# STM32_IO.net
KiCad netlist of a schematic drawn in Altium Designer
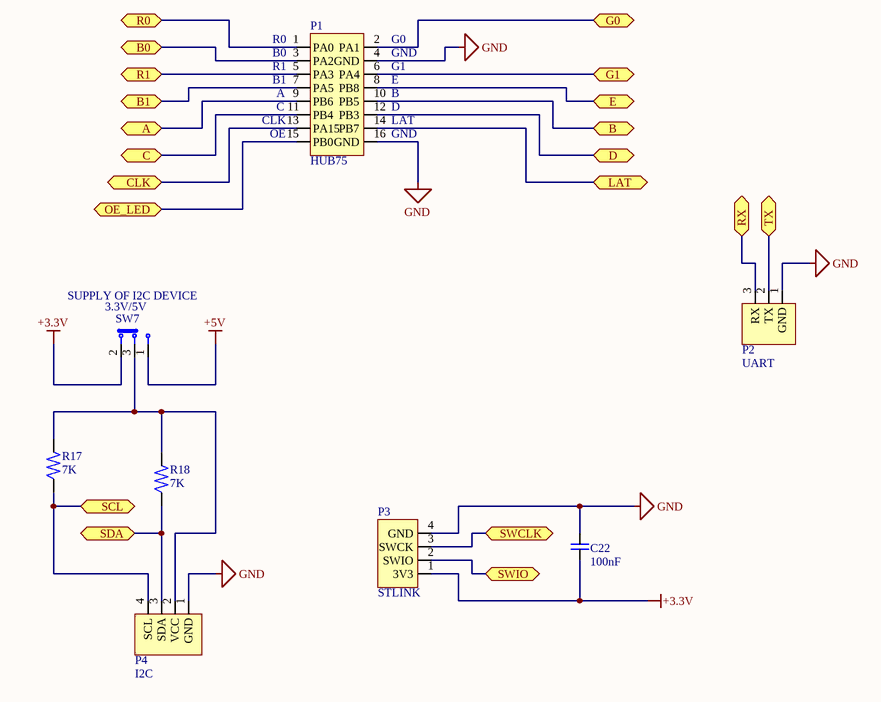
[diagram p0: STM32_IO.SchDoc]

(export (version "E")
  (design (tool "Eeschema 10.0.6"))
  (components
    (comp (ref "C22")
      (value "100nF")
      (footprint "SMT_CAP_MODEL_1206(3216)_SAMSUNG")
      (description "SMT Samsung Ceramic Capacitor MODEL *V *nF 1206(3216)  CL31B104KBCNNNC(etc.)")
      (libsource (lib "SMT_CAP_MODEL_1206(3216)_SAMSUNG") (part "SMT_CAP_MODEL_1206(3216)_SAMSUNG"))
    )
    (comp (ref "P1")
      (value "HUB75")
      (footprint "THT_CON_2316S-16G")
      (description "Connector 2316S-16G 16 Pin 2.54 Pitch")
      (libsource (lib "THT_CON_2316S-16G") (part "THT_CON_2316S-16G"))
    )
    (comp (ref "P2")
      (value "UART")
      (footprint "SMT_CON_STRAIGHT_2417SJ-03-SM2")
      (description "Connector 3P NELTRON 2417SJ-03-SM2-CR 100V/2A 2.0mm Pitch SMT")
      (libsource (lib "SMT_CON_STRAIGHT_2417SJ-03-SM2") (part "SMT_CON_STRAIGHT_2417SJ-03-SM2"))
    )
    (comp (ref "P3")
      (value "STLINK")
      (footprint "THT_STLINK_HEADER_4P_MALE")
      (description "Dupont Header Male STLINK 4P 2.54 Pitch")
      (libsource (lib "THT_STLINK_HEADER_4P_MALE") (part "THT_STLINK_HEADER_4P_MALE"))
    )
    (comp (ref "P4")
      (value "I2C")
      (footprint "SMT_CON_STRAIGHT_2417SJ-04-SM2")
      (description "Connector 4P NELTRON 2417SJ-04-SM2-CR 100V/2A 2.0mm Pitch SMT")
      (libsource (lib "SMT_CON_STRAIGHT_2417SJ-04-SM2") (part "SMT_CON_STRAIGHT_2417SJ-04-SM2"))
    )
    (comp (ref "R17")
      (value "7K")
      (footprint "SMT_RES_MODEL_1206(3216)_ROHM")
      (description "SMT ROHM Resistor MODEL 1206(3216) 1/4W MCR18ERTJ000")
      (libsource (lib "SMT_RES_MODEL_1206(3216)_ROHM") (part "SMT_RES_MODEL_1206(3216)_ROHM"))
    )
    (comp (ref "R18")
      (value "7K")
      (footprint "SMT_RES_MODEL_1206(3216)_ROHM")
      (description "SMT ROHM Resistor MODEL 1206(3216) 1/4W MCR18ERTJ000")
      (libsource (lib "SMT_RES_MODEL_1206(3216)_ROHM") (part "SMT_RES_MODEL_1206(3216)_ROHM"))
    )
    (comp (ref "SW7")
      (value "3.3V/5V")
      (footprint "THT_SSW_ESP1010")
      (description "Slide Switch ESP1010 12V 0.5A")
      (libsource (lib "THT_SSW_ESP1010") (part "THT_SSW_ESP1010"))
    )
  )
  (nets
    (net (code "1") (name "+3.3V") (class "Default")
      (node (ref "C22") (pin "1") (pinfunction "1_1") (pintype "passive"))
      (node (ref "P3") (pin "1") (pinfunction "3V3_1") (pintype "passive"))
      (node (ref "SW7") (pin "2") (pinfunction "2_2") (pintype "passive"))
    )
    (net (code "2") (name "+5V") (class "Default")
      (node (ref "SW7") (pin "1") (pinfunction "1_1") (pintype "passive"))
    )
    (net (code "3") (name "/A") (class "Default")
      (node (ref "P1") (pin "9") (pinfunction "PB6_9") (pintype "passive"))
    )
    (net (code "4") (name "/B") (class "Default")
      (node (ref "P1") (pin "10") (pinfunction "PB5_10") (pintype "passive"))
    )
    (net (code "5") (name "/B0") (class "Default")
      (node (ref "P1") (pin "3") (pinfunction "PA2_3") (pintype "passive"))
    )
    (net (code "6") (name "/B1") (class "Default")
      (node (ref "P1") (pin "7") (pinfunction "PA5_7") (pintype "passive"))
    )
    (net (code "7") (name "/C") (class "Default")
      (node (ref "P1") (pin "11") (pinfunction "PB4_11") (pintype "passive"))
    )
    (net (code "8") (name "/CLK") (class "Default")
      (node (ref "P1") (pin "13") (pinfunction "PA15_13") (pintype "passive"))
    )
    (net (code "9") (name "/D") (class "Default")
      (node (ref "P1") (pin "12") (pinfunction "PB3_12") (pintype "passive"))
    )
    (net (code "10") (name "/E") (class "Default")
      (node (ref "P1") (pin "8") (pinfunction "PB8_8") (pintype "passive"))
    )
    (net (code "11") (name "/G0") (class "Default")
      (node (ref "P1") (pin "2") (pinfunction "PA1_2") (pintype "passive"))
    )
    (net (code "12") (name "/G1") (class "Default")
      (node (ref "P1") (pin "6") (pinfunction "PA4_6") (pintype "passive"))
    )
    (net (code "13") (name "/LAT") (class "Default")
      (node (ref "P1") (pin "14") (pinfunction "PB7_14") (pintype "passive"))
    )
    (net (code "14") (name "/OE_LED") (class "Default")
      (node (ref "P1") (pin "15") (pinfunction "PB0_15") (pintype "passive"))
    )
    (net (code "15") (name "/R0") (class "Default")
      (node (ref "P1") (pin "1") (pinfunction "PA0_1") (pintype "passive"))
    )
    (net (code "16") (name "/R1") (class "Default")
      (node (ref "P1") (pin "5") (pinfunction "PA3_5") (pintype "passive"))
    )
    (net (code "17") (name "/RX") (class "Default")
      (node (ref "P2") (pin "3") (pinfunction "RX_3") (pintype "passive"))
    )
    (net (code "18") (name "/SCL") (class "Default")
      (node (ref "P4") (pin "4") (pinfunction "SCL_4") (pintype "passive"))
      (node (ref "R17") (pin "2") (pinfunction "2_2") (pintype "passive"))
    )
    (net (code "19") (name "/SDA") (class "Default")
      (node (ref "P4") (pin "3") (pinfunction "SDA_3") (pintype "passive"))
      (node (ref "R18") (pin "2") (pinfunction "2_2") (pintype "passive"))
    )
    (net (code "20") (name "/SWCLK") (class "Default")
      (node (ref "P3") (pin "3") (pinfunction "SWCK_3") (pintype "passive"))
    )
    (net (code "21") (name "/SWIO") (class "Default")
      (node (ref "P3") (pin "2") (pinfunction "SWIO_2") (pintype "passive"))
    )
    (net (code "22") (name "/TX") (class "Default")
      (node (ref "P2") (pin "2") (pinfunction "TX_2") (pintype "passive"))
    )
    (net (code "23") (name "GND") (class "Default")
      (node (ref "C22") (pin "2") (pinfunction "2_2") (pintype "passive"))
      (node (ref "P1") (pin "16") (pinfunction "GND_16") (pintype "passive"))
      (node (ref "P1") (pin "4") (pinfunction "GND_4") (pintype "passive"))
      (node (ref "P2") (pin "1") (pinfunction "GND_1") (pintype "passive"))
      (node (ref "P3") (pin "4") (pinfunction "GND_4") (pintype "passive"))
      (node (ref "P4") (pin "1") (pinfunction "GND_1") (pintype "passive"))
    )
    (net (code "24") (name "Net-(P4-VCC)") (class "Default")
      (node (ref "P4") (pin "2") (pinfunction "VCC_2") (pintype "passive"))
      (node (ref "R17") (pin "1") (pinfunction "1_1") (pintype "passive"))
      (node (ref "R18") (pin "1") (pinfunction "1_1") (pintype "passive"))
      (node (ref "SW7") (pin "3") (pinfunction "3_3") (pintype "passive"))
    )
  )
)
